# MB_FPGA.net
KiCad netlist of a schematic drawn in Altium Designer
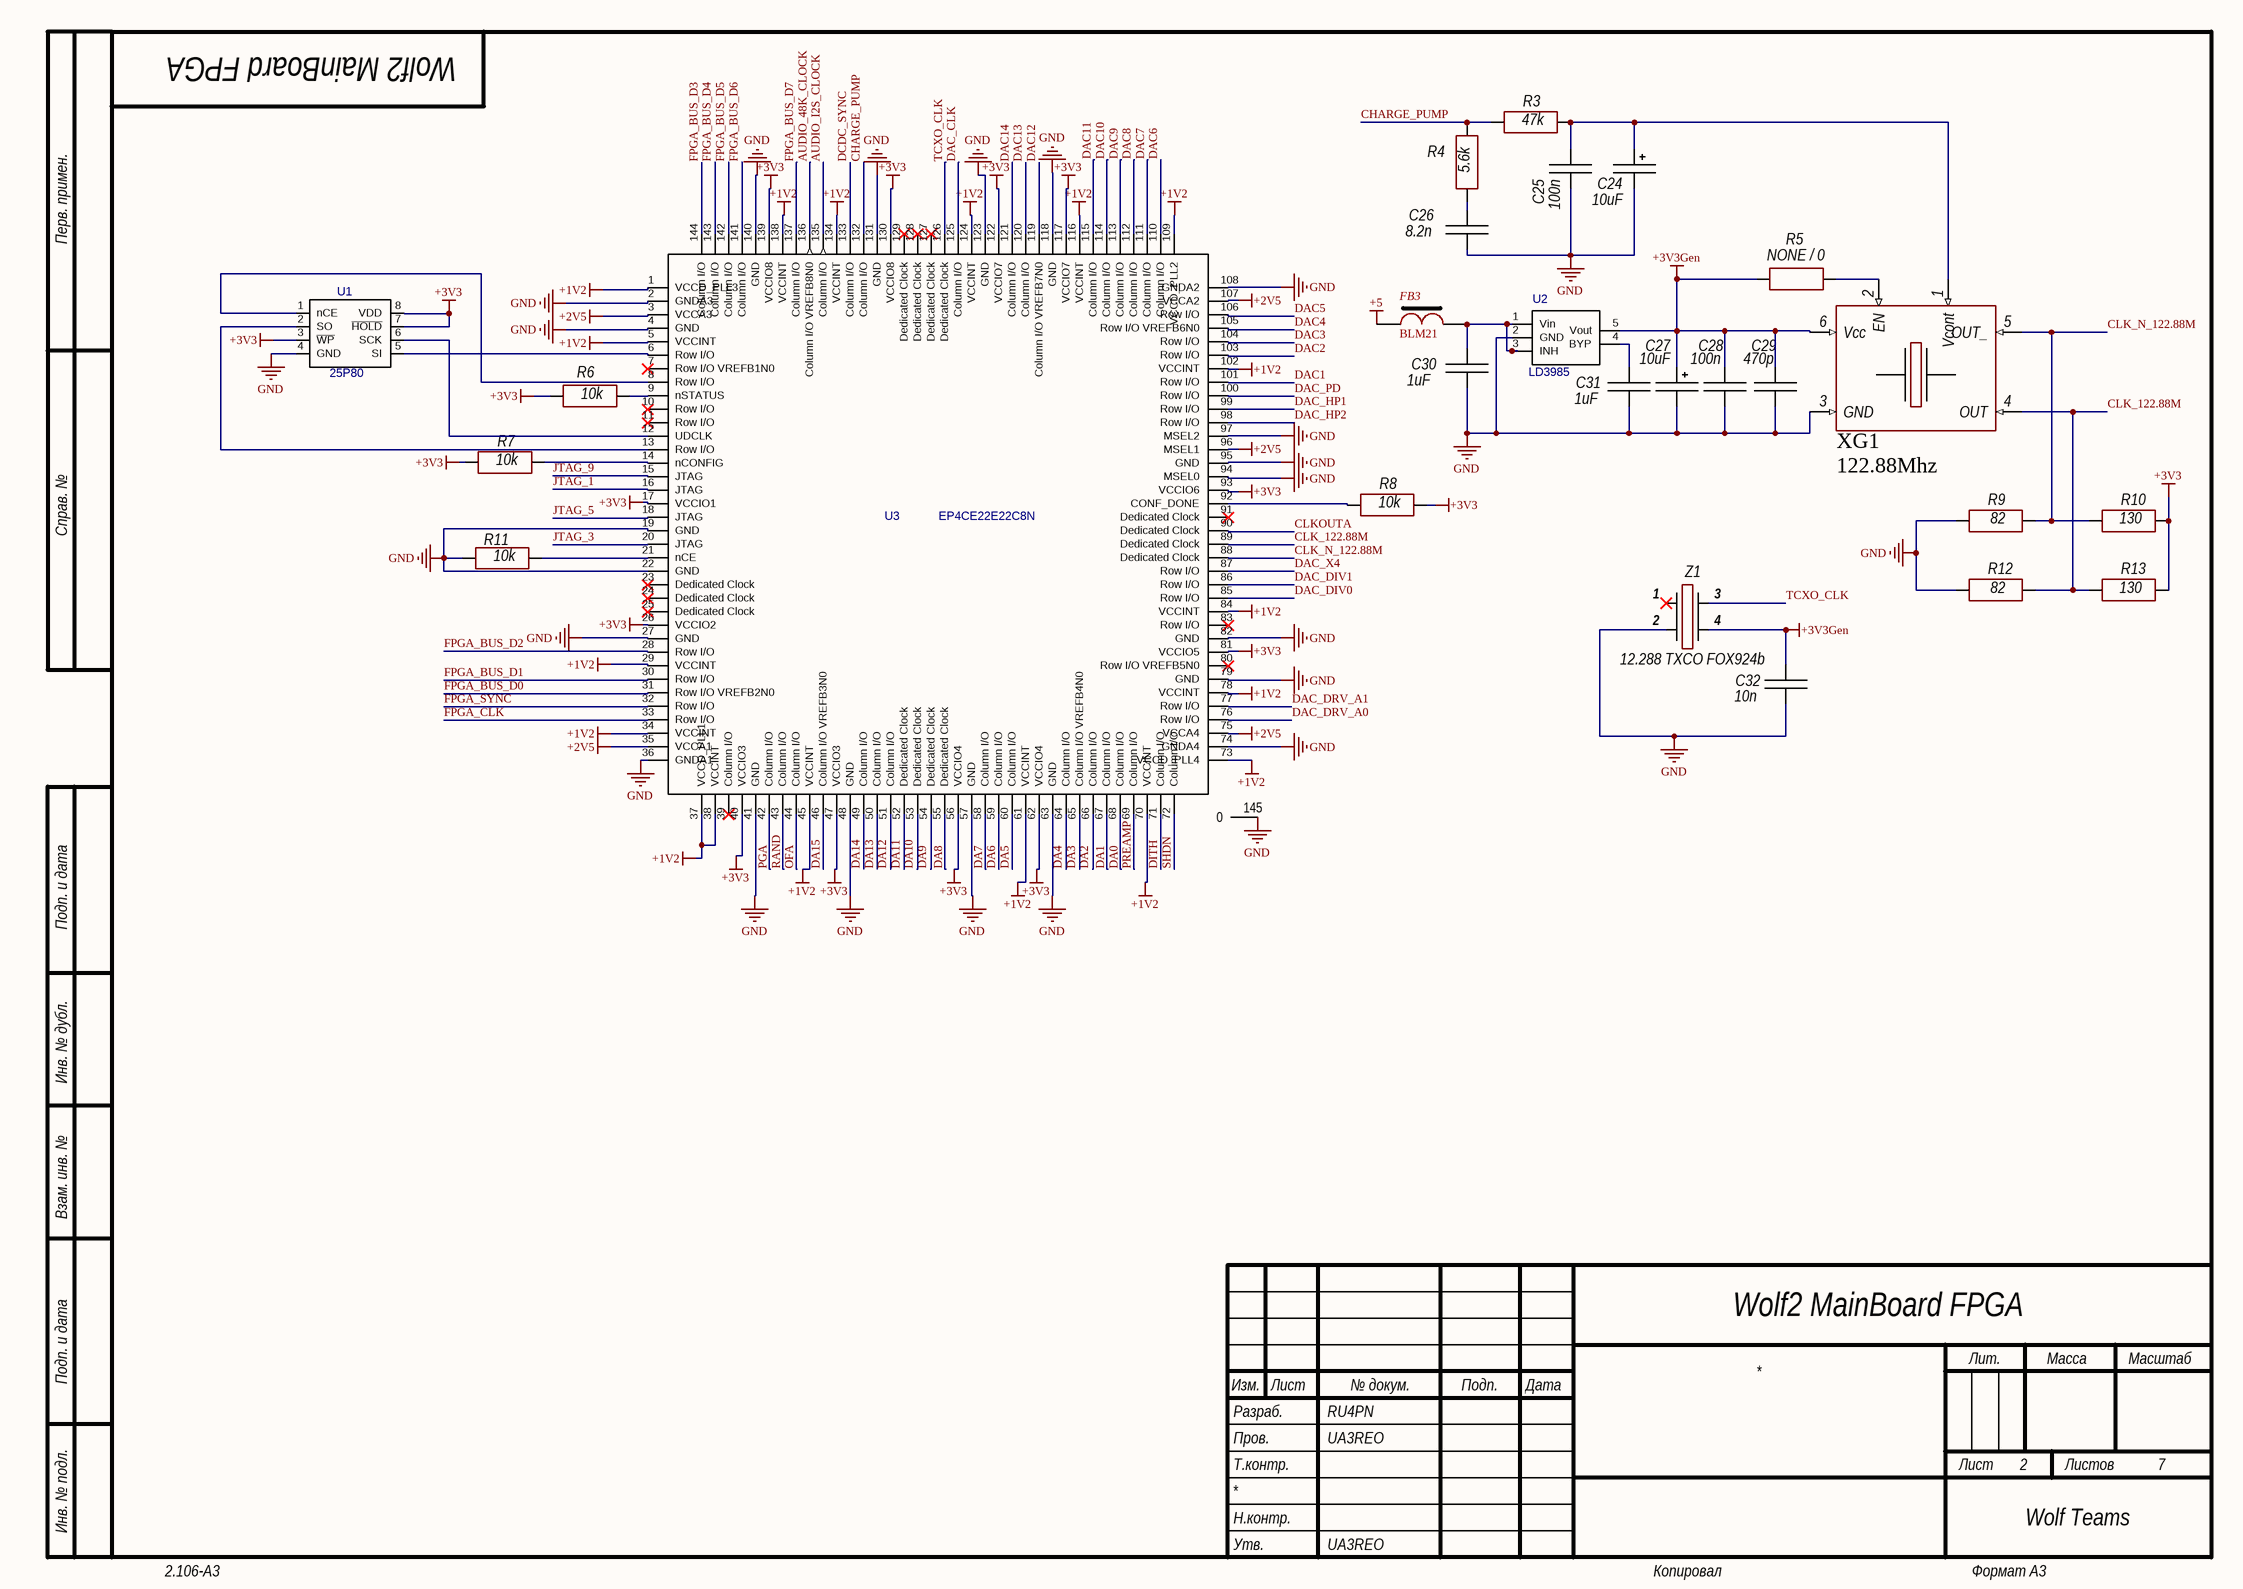
[diagram p0: MB_FPGA.SchDoc]

(export (version "E")
  (design (tool "Eeschema 10.0.6"))
  (components
    (comp (ref "C24")
      (value "10uF")
      (footprint "standard:TANTAL_B")
      (libsource (lib "Discrete") (part "TantalCap"))
    )
    (comp (ref "C25")
      (value "100n")
      (footprint "standard:CH0805C")
      (libsource (lib "Discrete") (part "Capacitor"))
    )
    (comp (ref "C26")
      (value "8.2n")
      (footprint "standard:CH0805C")
      (libsource (lib "Discrete") (part "Capacitor"))
    )
    (comp (ref "C27")
      (value "10uF")
      (footprint "standard:TANTAL_B")
      (libsource (lib "Discrete") (part "TantalCap"))
    )
    (comp (ref "C28")
      (value "100n")
      (footprint "standard:CH0805C")
      (libsource (lib "Discrete") (part "Capacitor"))
    )
    (comp (ref "C29")
      (value "470p")
      (footprint "standard:CH0805C")
      (libsource (lib "Discrete") (part "Capacitor"))
    )
    (comp (ref "C30")
      (value "1uF")
      (footprint "standard:CH0805C")
      (libsource (lib "Discrete") (part "Capacitor"))
    )
    (comp (ref "C31")
      (value "1uF")
      (footprint "standard:CH0805C")
      (libsource (lib "Discrete") (part "Capacitor"))
    )
    (comp (ref "C32")
      (value "10n")
      (footprint "standard:CH0805C")
      (libsource (lib "Discrete") (part "Capacitor"))
    )
    (comp (ref "FB3") (value "BLM21") (footprint "CH0805L") (libsource (lib "Discrete") (part "FB-1")))
    (comp (ref "R3")
      (value "47k")
      (footprint "standard:CH0805R")
      (libsource (lib "Discrete") (part "Resistor"))
    )
    (comp (ref "R4") (value "5.6k") (footprint "standard:CH0805R") (libsource (lib "") (part "Resistor_1")))
    (comp (ref "R5")
      (value "NONE / 0")
      (footprint "standard:CH0805R")
      (libsource (lib "Discrete") (part "Resistor"))
    )
    (comp (ref "R6")
      (value "10k")
      (footprint "standard:CH0805R")
      (libsource (lib "Discrete") (part "Resistor"))
    )
    (comp (ref "R7")
      (value "10k")
      (footprint "standard:CH0805R")
      (libsource (lib "Discrete") (part "Resistor"))
    )
    (comp (ref "R8")
      (value "10k")
      (footprint "standard:CH0805R")
      (libsource (lib "Discrete") (part "Resistor"))
    )
    (comp (ref "R9")
      (value "82")
      (footprint "standard:CH0805R")
      (libsource (lib "Discrete") (part "Resistor"))
    )
    (comp (ref "R10")
      (value "130")
      (footprint "standard:CH0805R")
      (libsource (lib "Discrete") (part "Resistor"))
    )
    (comp (ref "R11")
      (value "10k")
      (footprint "standard:CH0805R")
      (libsource (lib "Discrete") (part "Resistor"))
    )
    (comp (ref "R12")
      (value "82")
      (footprint "standard:CH0805R")
      (libsource (lib "Discrete") (part "Resistor"))
    )
    (comp (ref "R13")
      (value "130")
      (footprint "standard:CH0805R")
      (libsource (lib "Discrete") (part "Resistor"))
    )
    (comp (ref "U1") (value "25P80") (footprint "25P80") (libsource (lib "*") (part "25P80")))
    (comp (ref "U2") (value "LD3985") (footprint "LD3985") (libsource (lib "*") (part "LD3985")))
    (comp (ref "U3")
      (value "EP4CE22E22C8N")
      (footprint "QFP144-20-2222A")
      (libsource (lib "*") (part "EP4CE22E22C8N"))
    )
    (comp (ref "XG1")
      (value "122.88Mhz")
      (footprint "OCS: GENA")
      (description "Generator")
      (libsource (lib "Digital") (part "NV7050SA"))
    )
    (comp (ref "Z1")
      (value "12.288 TXCO FOX924b")
      (footprint "TCXO")
      (libsource (lib "Discrete") (part "Generator"))
    )
  )
  (nets
    (net (code "1") (name "+1V2") (class "Default")
      (node (ref "U3") (pin "1") (pinfunction "VCCD_PLL3_1") (pintype "passive"))
      (node (ref "U3") (pin "102") (pinfunction "VCCINT_102") (pintype "passive"))
      (node (ref "U3") (pin "109") (pinfunction "VCCD_PLL2_109") (pintype "passive"))
      (node (ref "U3") (pin "116") (pinfunction "VCCINT_116") (pintype "passive"))
      (node (ref "U3") (pin "124") (pinfunction "VCCINT_124") (pintype "passive"))
      (node (ref "U3") (pin "134") (pinfunction "VCCINT_134") (pintype "passive"))
      (node (ref "U3") (pin "138") (pinfunction "VCCINT_138") (pintype "passive"))
      (node (ref "U3") (pin "29") (pinfunction "VCCINT_29") (pintype "passive"))
      (node (ref "U3") (pin "34") (pinfunction "VCCINT_34") (pintype "passive"))
      (node (ref "U3") (pin "37") (pinfunction "VCCD_PLL1_37") (pintype "passive"))
      (node (ref "U3") (pin "38") (pinfunction "VCCINT_38") (pintype "passive"))
      (node (ref "U3") (pin "45") (pinfunction "VCCINT_45") (pintype "passive"))
      (node (ref "U3") (pin "5") (pinfunction "VCCINT_5") (pintype "passive"))
      (node (ref "U3") (pin "61") (pinfunction "VCCINT_61") (pintype "passive"))
      (node (ref "U3") (pin "70") (pinfunction "VCCINT_70") (pintype "passive"))
      (node (ref "U3") (pin "73") (pinfunction "VCCD_PLL4_73") (pintype "passive"))
      (node (ref "U3") (pin "78") (pinfunction "VCCINT_78") (pintype "passive"))
      (node (ref "U3") (pin "84") (pinfunction "VCCINT_84") (pintype "passive"))
    )
    (net (code "2") (name "+2V5") (class "Default")
      (node (ref "U3") (pin "107") (pinfunction "VCCA2_107") (pintype "passive"))
      (node (ref "U3") (pin "3") (pinfunction "VCCA3_3") (pintype "passive"))
      (node (ref "U3") (pin "35") (pinfunction "VCCA1_35") (pintype "passive"))
      (node (ref "U3") (pin "75") (pinfunction "VCCA4_75") (pintype "passive"))
      (node (ref "U3") (pin "96") (pinfunction "MSEL1_96") (pintype "passive"))
    )
    (net (code "3") (name "+3V3") (class "Default")
      (node (ref "R10") (pin "1") (pinfunction "1_1") (pintype "passive"))
      (node (ref "R13") (pin "1") (pinfunction "1_1") (pintype "passive"))
      (node (ref "R6") (pin "2") (pinfunction "2_2") (pintype "passive"))
      (node (ref "R7") (pin "2") (pinfunction "2_2") (pintype "passive"))
      (node (ref "R8") (pin "1") (pinfunction "1_1") (pintype "passive"))
      (node (ref "U1") (pin "3") (pinfunction "~{WP}_3") (pintype "passive"))
      (node (ref "U1") (pin "7") (pinfunction "~{HOLD}_7") (pintype "passive"))
      (node (ref "U1") (pin "8") (pinfunction "VDD_8") (pintype "passive"))
      (node (ref "U3") (pin "117") (pinfunction "VCCIO7_117") (pintype "passive"))
      (node (ref "U3") (pin "122") (pinfunction "VCCIO7_122") (pintype "passive"))
      (node (ref "U3") (pin "130") (pinfunction "VCCIO8_130") (pintype "passive"))
      (node (ref "U3") (pin "139") (pinfunction "VCCIO8_139") (pintype "passive"))
      (node (ref "U3") (pin "17") (pinfunction "VCCIO1_17") (pintype "passive"))
      (node (ref "U3") (pin "26") (pinfunction "VCCIO2_26") (pintype "passive"))
      (node (ref "U3") (pin "40") (pinfunction "VCCIO3_40") (pintype "passive"))
      (node (ref "U3") (pin "47") (pinfunction "VCCIO3_47") (pintype "passive"))
      (node (ref "U3") (pin "56") (pinfunction "VCCIO4_56") (pintype "passive"))
      (node (ref "U3") (pin "62") (pinfunction "VCCIO4_62") (pintype "passive"))
      (node (ref "U3") (pin "81") (pinfunction "VCCIO5_81") (pintype "passive"))
      (node (ref "U3") (pin "93") (pinfunction "VCCIO6_93") (pintype "passive"))
    )
    (net (code "4") (name "+3V3Gen") (class "Default")
      (node (ref "C27") (pin "1") (pinfunction "1_1") (pintype "power_in"))
      (node (ref "C28") (pin "1") (pinfunction "1_1") (pintype "power_in"))
      (node (ref "C29") (pin "1") (pinfunction "1_1") (pintype "power_in"))
      (node (ref "C32") (pin "1") (pinfunction "1_1") (pintype "power_in"))
      (node (ref "R5") (pin "2") (pinfunction "2_2") (pintype "passive"))
      (node (ref "U2") (pin "5") (pinfunction "Vout_5") (pintype "passive"))
      (node (ref "XG1") (pin "6") (pinfunction "Vcc_6") (pintype "input"))
      (node (ref "Z1") (pin "4") (pinfunction "4_4") (pintype "passive"))
    )
    (net (code "5") (name "+5") (class "Default")
      (node (ref "FB3") (pin "2") (pinfunction "2_2") (pintype "passive"))
    )
    (net (code "6") (name "/AUDIO_48K_CLOCK") (class "Default")
      (node (ref "U3") (pin "136") (pinfunction "Column_I/O_VREFB8N0_136") (pintype "output"))
    )
    (net (code "7") (name "/AUDIO_I2S_CLOCK") (class "Default")
      (node (ref "U3") (pin "135") (pinfunction "Column_I/O_135") (pintype "output"))
    )
    (net (code "8") (name "/CHARGE_PUMP") (class "Default")
      (node (ref "R3") (pin "2") (pinfunction "2_2") (pintype "passive"))
      (node (ref "R4") (pin "1") (pinfunction "1_1") (pintype "passive"))
      (node (ref "U3") (pin "132") (pinfunction "Column_I/O_132") (pintype "passive"))
    )
    (net (code "9") (name "/CLKOUTA") (class "Default")
      (node (ref "U3") (pin "90") (pinfunction "Dedicated_Clock_90") (pintype "passive"))
    )
    (net (code "10") (name "/CLK_122.88M") (class "Default")
      (node (ref "R12") (pin "1") (pinfunction "1_1") (pintype "passive"))
      (node (ref "R13") (pin "2") (pinfunction "2_2") (pintype "passive"))
      (node (ref "U3") (pin "89") (pinfunction "Dedicated_Clock_89") (pintype "passive"))
      (node (ref "XG1") (pin "4") (pinfunction "OUT_4") (pintype "input"))
    )
    (net (code "11") (name "/CLK_N_122.88M") (class "Default")
      (node (ref "R10") (pin "2") (pinfunction "2_2") (pintype "passive"))
      (node (ref "R9") (pin "1") (pinfunction "1_1") (pintype "passive"))
      (node (ref "U3") (pin "88") (pinfunction "Dedicated_Clock_88") (pintype "passive"))
      (node (ref "XG1") (pin "5") (pinfunction "OUT__5") (pintype "input"))
    )
    (net (code "12") (name "/DA0") (class "Default")
      (node (ref "U3") (pin "68") (pinfunction "Column_I/O_68") (pintype "passive"))
    )
    (net (code "13") (name "/DA1") (class "Default")
      (node (ref "U3") (pin "67") (pinfunction "Column_I/O_67") (pintype "passive"))
    )
    (net (code "14") (name "/DA2") (class "Default")
      (node (ref "U3") (pin "66") (pinfunction "Column_I/O_66") (pintype "passive"))
    )
    (net (code "15") (name "/DA3") (class "Default")
      (node (ref "U3") (pin "65") (pinfunction "Column_I/O_VREFB4N0_65") (pintype "passive"))
    )
    (net (code "16") (name "/DA4") (class "Default")
      (node (ref "U3") (pin "64") (pinfunction "Column_I/O_64") (pintype "passive"))
    )
    (net (code "17") (name "/DA5") (class "Default")
      (node (ref "U3") (pin "60") (pinfunction "Column_I/O_60") (pintype "passive"))
    )
    (net (code "18") (name "/DA6") (class "Default")
      (node (ref "U3") (pin "59") (pinfunction "Column_I/O_59") (pintype "passive"))
    )
    (net (code "19") (name "/DA7") (class "Default")
      (node (ref "U3") (pin "58") (pinfunction "Column_I/O_58") (pintype "passive"))
    )
    (net (code "20") (name "/DA8") (class "Default")
      (node (ref "U3") (pin "55") (pinfunction "Dedicated_Clock_55") (pintype "passive"))
    )
    (net (code "21") (name "/DA9") (class "Default")
      (node (ref "U3") (pin "54") (pinfunction "Dedicated_Clock_54") (pintype "passive"))
    )
    (net (code "22") (name "/DA10") (class "Default")
      (node (ref "U3") (pin "53") (pinfunction "Dedicated_Clock_53") (pintype "passive"))
    )
    (net (code "23") (name "/DA11") (class "Default")
      (node (ref "U3") (pin "52") (pinfunction "Dedicated_Clock_52") (pintype "passive"))
    )
    (net (code "24") (name "/DA12") (class "Default")
      (node (ref "U3") (pin "51") (pinfunction "Column_I/O_51") (pintype "passive"))
    )
    (net (code "25") (name "/DA13") (class "Default")
      (node (ref "U3") (pin "50") (pinfunction "Column_I/O_50") (pintype "passive"))
    )
    (net (code "26") (name "/DA14") (class "Default")
      (node (ref "U3") (pin "49") (pinfunction "Column_I/O_49") (pintype "passive"))
    )
    (net (code "27") (name "/DA15") (class "Default")
      (node (ref "U3") (pin "46") (pinfunction "Column_I/O_VREFB3N0_46") (pintype "passive"))
    )
    (net (code "28") (name "/DAC1") (class "Default")
      (node (ref "U3") (pin "101") (pinfunction "Row_I/O_101") (pintype "passive"))
    )
    (net (code "29") (name "/DAC2") (class "Default")
      (node (ref "U3") (pin "103") (pinfunction "Row_I/O_103") (pintype "passive"))
    )
    (net (code "30") (name "/DAC3") (class "Default")
      (node (ref "U3") (pin "104") (pinfunction "Row_I/O_104") (pintype "passive"))
    )
    (net (code "31") (name "/DAC4") (class "Default")
      (node (ref "U3") (pin "105") (pinfunction "Row_I/O_VREFB6N0_105") (pintype "passive"))
    )
    (net (code "32") (name "/DAC5") (class "Default")
      (node (ref "U3") (pin "106") (pinfunction "Row_I/O_106") (pintype "passive"))
    )
    (net (code "33") (name "/DAC6") (class "Default")
      (node (ref "U3") (pin "110") (pinfunction "Column_I/O_110") (pintype "passive"))
    )
    (net (code "34") (name "/DAC7") (class "Default")
      (node (ref "U3") (pin "111") (pinfunction "Column_I/O_111") (pintype "passive"))
    )
    (net (code "35") (name "/DAC8") (class "Default")
      (node (ref "U3") (pin "112") (pinfunction "Column_I/O_112") (pintype "passive"))
    )
    (net (code "36") (name "/DAC9") (class "Default")
      (node (ref "U3") (pin "113") (pinfunction "Column_I/O_113") (pintype "passive"))
    )
    (net (code "37") (name "/DAC10") (class "Default")
      (node (ref "U3") (pin "114") (pinfunction "Column_I/O_114") (pintype "passive"))
    )
    (net (code "38") (name "/DAC11") (class "Default")
      (node (ref "U3") (pin "115") (pinfunction "Column_I/O_115") (pintype "passive"))
    )
    (net (code "39") (name "/DAC12") (class "Default")
      (node (ref "U3") (pin "119") (pinfunction "Column_I/O_VREFB7N0_119") (pintype "passive"))
    )
    (net (code "40") (name "/DAC13") (class "Default")
      (node (ref "U3") (pin "120") (pinfunction "Column_I/O_120") (pintype "passive"))
    )
    (net (code "41") (name "/DAC14") (class "Default")
      (node (ref "U3") (pin "121") (pinfunction "Column_I/O_121") (pintype "passive"))
    )
    (net (code "42") (name "/DAC_CLK") (class "Default")
      (node (ref "U3") (pin "125") (pinfunction "Column_I/O_125") (pintype "passive"))
    )
    (net (code "43") (name "/DAC_DIV0") (class "Default")
      (node (ref "U3") (pin "85") (pinfunction "Row_I/O_85") (pintype "passive"))
    )
    (net (code "44") (name "/DAC_DIV1") (class "Default")
      (node (ref "U3") (pin "86") (pinfunction "Row_I/O_86") (pintype "passive"))
    )
    (net (code "45") (name "/DAC_DRV_A0") (class "Default")
      (node (ref "U3") (pin "76") (pinfunction "Row_I/O_76") (pintype "passive"))
    )
    (net (code "46") (name "/DAC_DRV_A1") (class "Default")
      (node (ref "U3") (pin "77") (pinfunction "Row_I/O_77") (pintype "passive"))
    )
    (net (code "47") (name "/DAC_HP1") (class "Default")
      (node (ref "U3") (pin "99") (pinfunction "Row_I/O_99") (pintype "passive"))
    )
    (net (code "48") (name "/DAC_HP2") (class "Default")
      (node (ref "U3") (pin "98") (pinfunction "Row_I/O_98") (pintype "passive"))
    )
    (net (code "49") (name "/DAC_PD") (class "Default")
      (node (ref "U3") (pin "100") (pinfunction "Row_I/O_100") (pintype "passive"))
    )
    (net (code "50") (name "/DAC_X4") (class "Default")
      (node (ref "U3") (pin "87") (pinfunction "Row_I/O_87") (pintype "passive"))
    )
    (net (code "51") (name "/DCDC_SYNC") (class "Default")
      (node (ref "U3") (pin "133") (pinfunction "Column_I/O_133") (pintype "passive"))
    )
    (net (code "52") (name "/DITH") (class "Default")
      (node (ref "U3") (pin "71") (pinfunction "Column_I/O_71") (pintype "passive"))
    )
    (net (code "53") (name "/FPGA_BUS_D0") (class "Default")
      (node (ref "U3") (pin "31") (pinfunction "Row_I/O_VREFB2N0_31") (pintype "passive"))
    )
    (net (code "54") (name "/FPGA_BUS_D1") (class "Default")
      (node (ref "U3") (pin "30") (pinfunction "Row_I/O_30") (pintype "passive"))
    )
    (net (code "55") (name "/FPGA_BUS_D2") (class "Default")
      (node (ref "U3") (pin "28") (pinfunction "Row_I/O_28") (pintype "passive"))
    )
    (net (code "56") (name "/FPGA_BUS_D3") (class "Default")
      (node (ref "U3") (pin "144") (pinfunction "Column_I/O_144") (pintype "passive"))
    )
    (net (code "57") (name "/FPGA_BUS_D4") (class "Default")
      (node (ref "U3") (pin "143") (pinfunction "Column_I/O_143") (pintype "passive"))
    )
    (net (code "58") (name "/FPGA_BUS_D5") (class "Default")
      (node (ref "U3") (pin "142") (pinfunction "Column_I/O_142") (pintype "passive"))
    )
    (net (code "59") (name "/FPGA_BUS_D6") (class "Default")
      (node (ref "U3") (pin "141") (pinfunction "Column_I/O_141") (pintype "passive"))
    )
    (net (code "60") (name "/FPGA_BUS_D7") (class "Default")
      (node (ref "U3") (pin "137") (pinfunction "Column_I/O_137") (pintype "passive"))
    )
    (net (code "61") (name "/FPGA_CLK") (class "Default")
      (node (ref "U3") (pin "33") (pinfunction "Row_I/O_33") (pintype "passive"))
    )
    (net (code "62") (name "/FPGA_SYNC") (class "Default")
      (node (ref "U3") (pin "32") (pinfunction "Row_I/O_32") (pintype "passive"))
    )
    (net (code "63") (name "/JTAG_1") (class "Default")
      (node (ref "U3") (pin "16") (pinfunction "JTAG_16") (pintype "passive"))
    )
    (net (code "64") (name "/JTAG_3") (class "Default")
      (node (ref "U3") (pin "20") (pinfunction "JTAG_20") (pintype "passive"))
    )
    (net (code "65") (name "/JTAG_5") (class "Default")
      (node (ref "U3") (pin "18") (pinfunction "JTAG_18") (pintype "passive"))
    )
    (net (code "66") (name "/JTAG_9") (class "Default")
      (node (ref "U3") (pin "15") (pinfunction "JTAG_15") (pintype "passive"))
    )
    (net (code "67") (name "/OFA") (class "Default")
      (node (ref "U3") (pin "44") (pinfunction "Column_I/O_44") (pintype "passive"))
    )
    (net (code "68") (name "/PGA") (class "Default")
      (node (ref "U3") (pin "42") (pinfunction "Column_I/O_42") (pintype "passive"))
    )
    (net (code "69") (name "/PREAMP") (class "Default")
      (node (ref "U3") (pin "69") (pinfunction "Column_I/O_69") (pintype "passive"))
    )
    (net (code "70") (name "/RAND") (class "Default")
      (node (ref "U3") (pin "43") (pinfunction "Column_I/O_43") (pintype "passive"))
    )
    (net (code "71") (name "/SHDN") (class "Default")
      (node (ref "U3") (pin "72") (pinfunction "Column_I/O_72") (pintype "passive"))
    )
    (net (code "72") (name "/TCXO_CLK") (class "Default")
      (node (ref "U3") (pin "126") (pinfunction "Dedicated_Clock_126") (pintype "passive"))
      (node (ref "Z1") (pin "3") (pinfunction "3_3") (pintype "passive"))
    )
    (net (code "73") (name "GND") (class "Default")
      (node (ref "C24") (pin "2") (pinfunction "2_2") (pintype "power_in"))
      (node (ref "C25") (pin "2") (pinfunction "2_2") (pintype "power_in"))
      (node (ref "C26") (pin "2") (pinfunction "2_2") (pintype "power_in"))
      (node (ref "C27") (pin "2") (pinfunction "2_2") (pintype "power_in"))
      (node (ref "C28") (pin "2") (pinfunction "2_2") (pintype "power_in"))
      (node (ref "C29") (pin "2") (pinfunction "2_2") (pintype "power_in"))
      (node (ref "C30") (pin "2") (pinfunction "2_2") (pintype "power_in"))
      (node (ref "C31") (pin "2") (pinfunction "2_2") (pintype "power_in"))
      (node (ref "C32") (pin "2") (pinfunction "2_2") (pintype "power_in"))
      (node (ref "R11") (pin "2") (pinfunction "2_2") (pintype "passive"))
      (node (ref "R12") (pin "2") (pinfunction "2_2") (pintype "passive"))
      (node (ref "R9") (pin "2") (pinfunction "2_2") (pintype "passive"))
      (node (ref "U1") (pin "4") (pinfunction "GND_4") (pintype "passive"))
      (node (ref "U2") (pin "2") (pinfunction "GND_2") (pintype "passive"))
      (node (ref "U3") (pin "108") (pinfunction "GNDA2_108") (pintype "passive"))
      (node (ref "U3") (pin "118") (pinfunction "GND_118") (pintype "passive"))
      (node (ref "U3") (pin "123") (pinfunction "GND_123") (pintype "passive"))
      (node (ref "U3") (pin "131") (pinfunction "GND_131") (pintype "passive"))
      (node (ref "U3") (pin "140") (pinfunction "GND_140") (pintype "passive"))
      (node (ref "U3") (pin "145") (pinfunction "0_145") (pintype "passive"))
      (node (ref "U3") (pin "19") (pinfunction "GND_19") (pintype "passive"))
      (node (ref "U3") (pin "2") (pinfunction "GNDA3_2") (pintype "passive"))
      (node (ref "U3") (pin "22") (pinfunction "GND_22") (pintype "passive"))
      (node (ref "U3") (pin "27") (pinfunction "GND_27") (pintype "passive"))
      (node (ref "U3") (pin "36") (pinfunction "GNDA1_36") (pintype "passive"))
      (node (ref "U3") (pin "4") (pinfunction "GND_4") (pintype "passive"))
      (node (ref "U3") (pin "41") (pinfunction "GND_41") (pintype "passive"))
      (node (ref "U3") (pin "48") (pinfunction "GND_48") (pintype "passive"))
      (node (ref "U3") (pin "57") (pinfunction "GND_57") (pintype "passive"))
      (node (ref "U3") (pin "63") (pinfunction "GND_63") (pintype "passive"))
      (node (ref "U3") (pin "74") (pinfunction "GNDA4_74") (pintype "passive"))
      (node (ref "U3") (pin "79") (pinfunction "GND_79") (pintype "passive"))
      (node (ref "U3") (pin "82") (pinfunction "GND_82") (pintype "passive"))
      (node (ref "U3") (pin "94") (pinfunction "MSEL0_94") (pintype "passive"))
      (node (ref "U3") (pin "95") (pinfunction "GND_95") (pintype "passive"))
      (node (ref "U3") (pin "97") (pinfunction "MSEL2_97") (pintype "passive"))
      (node (ref "XG1") (pin "3") (pinfunction "GND_3") (pintype "input"))
      (node (ref "Z1") (pin "2") (pinfunction "2_2") (pintype "passive"))
    )
    (net (code "74") (name "Net-(C26-Pad1)") (class "Default")
      (node (ref "C26") (pin "1") (pinfunction "1_1") (pintype "power_in"))
      (node (ref "R4") (pin "2") (pinfunction "2_2") (pintype "passive"))
    )
    (net (code "75") (name "Net-(U1-SCK)") (class "Default")
      (node (ref "U1") (pin "6") (pinfunction "SCK_6") (pintype "passive"))
      (node (ref "U3") (pin "12") (pinfunction "UDCLK_12") (pintype "passive"))
    )
    (net (code "76") (name "Net-(U1-SI)") (class "Default")
      (node (ref "U1") (pin "5") (pinfunction "SI_5") (pintype "passive"))
      (node (ref "U3") (pin "6") (pinfunction "Row_I/O_6") (pintype "passive"))
    )
    (net (code "77") (name "Net-(U1-SO)") (class "Default")
      (node (ref "U1") (pin "2") (pinfunction "SO_2") (pintype "passive"))
      (node (ref "U3") (pin "13") (pinfunction "Row_I/O_13") (pintype "passive"))
    )
    (net (code "78") (name "Net-(U1-nCE)") (class "Default")
      (node (ref "U1") (pin "1") (pinfunction "nCE_1") (pintype "passive"))
      (node (ref "U3") (pin "8") (pinfunction "Row_I/O_8") (pintype "passive"))
    )
    (net (code "79") (name "Net-(U2-BYP)") (class "Default")
      (node (ref "C31") (pin "1") (pinfunction "1_1") (pintype "power_in"))
      (node (ref "U2") (pin "4") (pinfunction "BYP_4") (pintype "passive"))
    )
    (net (code "80") (name "Net-(U2-INH)") (class "Default")
      (node (ref "C30") (pin "1") (pinfunction "1_1") (pintype "power_in"))
      (node (ref "FB3") (pin "1") (pinfunction "1_1") (pintype "passive"))
      (node (ref "U2") (pin "1") (pinfunction "Vin_1") (pintype "passive"))
      (node (ref "U2") (pin "3") (pinfunction "INH_3") (pintype "passive"))
    )
    (net (code "81") (name "Net-(U3-CONF_DONE)") (class "Default")
      (node (ref "R8") (pin "2") (pinfunction "2_2") (pintype "passive"))
      (node (ref "U3") (pin "92") (pinfunction "CONF_DONE_92") (pintype "passive"))
    )
    (net (code "82") (name "Net-(U3-nCE)") (class "Default")
      (node (ref "R11") (pin "1") (pinfunction "1_1") (pintype "passive"))
      (node (ref "U3") (pin "21") (pinfunction "nCE_21") (pintype "passive"))
    )
    (net (code "83") (name "Net-(U3-nCONFIG)") (class "Default")
      (node (ref "R7") (pin "1") (pinfunction "1_1") (pintype "passive"))
      (node (ref "U3") (pin "14") (pinfunction "nCONFIG_14") (pintype "passive"))
    )
    (net (code "84") (name "Net-(U3-nSTATUS)") (class "Default")
      (node (ref "R6") (pin "1") (pinfunction "1_1") (pintype "passive"))
      (node (ref "U3") (pin "9") (pinfunction "nSTATUS_9") (pintype "passive"))
    )
    (net (code "85") (name "Net-(XG1-EN)") (class "Default")
      (node (ref "R5") (pin "1") (pinfunction "1_1") (pintype "passive"))
      (node (ref "XG1") (pin "2") (pinfunction "EN_2") (pintype "input"))
    )
    (net (code "86") (name "Net-(XG1-Vcont)") (class "Default")
      (node (ref "C24") (pin "1") (pinfunction "1_1") (pintype "power_in"))
      (node (ref "C25") (pin "1") (pinfunction "1_1") (pintype "power_in"))
      (node (ref "R3") (pin "1") (pinfunction "1_1") (pintype "passive"))
      (node (ref "XG1") (pin "1") (pinfunction "Vcont_1") (pintype "input"))
    )
    (net (code "87") (name "unconnected-(U3-Column_I{slash}O-Pad39)") (class "Default")
      (node (ref "U3") (pin "39") (pinfunction "Column_I/O_39") (pintype "passive+no_connect"))
    )
    (net (code "88") (name "unconnected-(U3-Dedicated_Clock-Pad23)") (class "Default")
      (node (ref "U3") (pin "23") (pinfunction "Dedicated_Clock_23") (pintype "passive+no_connect"))
    )
    (net (code "89") (name "unconnected-(U3-Dedicated_Clock-Pad24)") (class "Default")
      (node (ref "U3") (pin "24") (pinfunction "Dedicated_Clock_24") (pintype "passive+no_connect"))
    )
    (net (code "90") (name "unconnected-(U3-Dedicated_Clock-Pad25)") (class "Default")
      (node (ref "U3") (pin "25") (pinfunction "Dedicated_Clock_25") (pintype "passive+no_connect"))
    )
    (net (code "91") (name "unconnected-(U3-Dedicated_Clock-Pad91)") (class "Default")
      (node (ref "U3") (pin "91") (pinfunction "Dedicated_Clock_91") (pintype "passive+no_connect"))
    )
    (net (code "92") (name "unconnected-(U3-Dedicated_Clock-Pad127)") (class "Default")
      (node (ref "U3") (pin "127") (pinfunction "Dedicated_Clock_127") (pintype "passive+no_connect"))
    )
    (net (code "93") (name "unconnected-(U3-Dedicated_Clock-Pad128)") (class "Default")
      (node (ref "U3") (pin "128") (pinfunction "Dedicated_Clock_128") (pintype "passive+no_connect"))
    )
    (net (code "94") (name "unconnected-(U3-Dedicated_Clock-Pad129)") (class "Default")
      (node (ref "U3") (pin "129") (pinfunction "Dedicated_Clock_129") (pintype "passive+no_connect"))
    )
    (net (code "95") (name "unconnected-(U3-Row_I{slash}O-Pad10)") (class "Default")
      (node (ref "U3") (pin "10") (pinfunction "Row_I/O_10") (pintype "passive+no_connect"))
    )
    (net (code "96") (name "unconnected-(U3-Row_I{slash}O-Pad11)") (class "Default")
      (node (ref "U3") (pin "11") (pinfunction "Row_I/O_11") (pintype "passive+no_connect"))
    )
    (net (code "97") (name "unconnected-(U3-Row_I{slash}O-Pad83)") (class "Default")
      (node (ref "U3") (pin "83") (pinfunction "Row_I/O_83") (pintype "passive+no_connect"))
    )
    (net (code "98") (name "unconnected-(U3-Row_I{slash}O_VREFB1N0-Pad7)") (class "Default")
      (node (ref "U3") (pin "7") (pinfunction "Row_I/O_VREFB1N0_7") (pintype "passive+no_connect"))
    )
    (net (code "99") (name "unconnected-(U3-Row_I{slash}O_VREFB5N0-Pad80)") (class "Default")
      (node (ref "U3") (pin "80") (pinfunction "Row_I/O_VREFB5N0_80") (pintype "passive+no_connect"))
    )
    (net (code "100") (name "unconnected-(Z1-Pad1)") (class "Default")
      (node (ref "Z1") (pin "1") (pinfunction "1_1") (pintype "passive+no_connect"))
    )
  )
)
